# design.net
KiCad netlist of a schematic drawn in Altium Designer
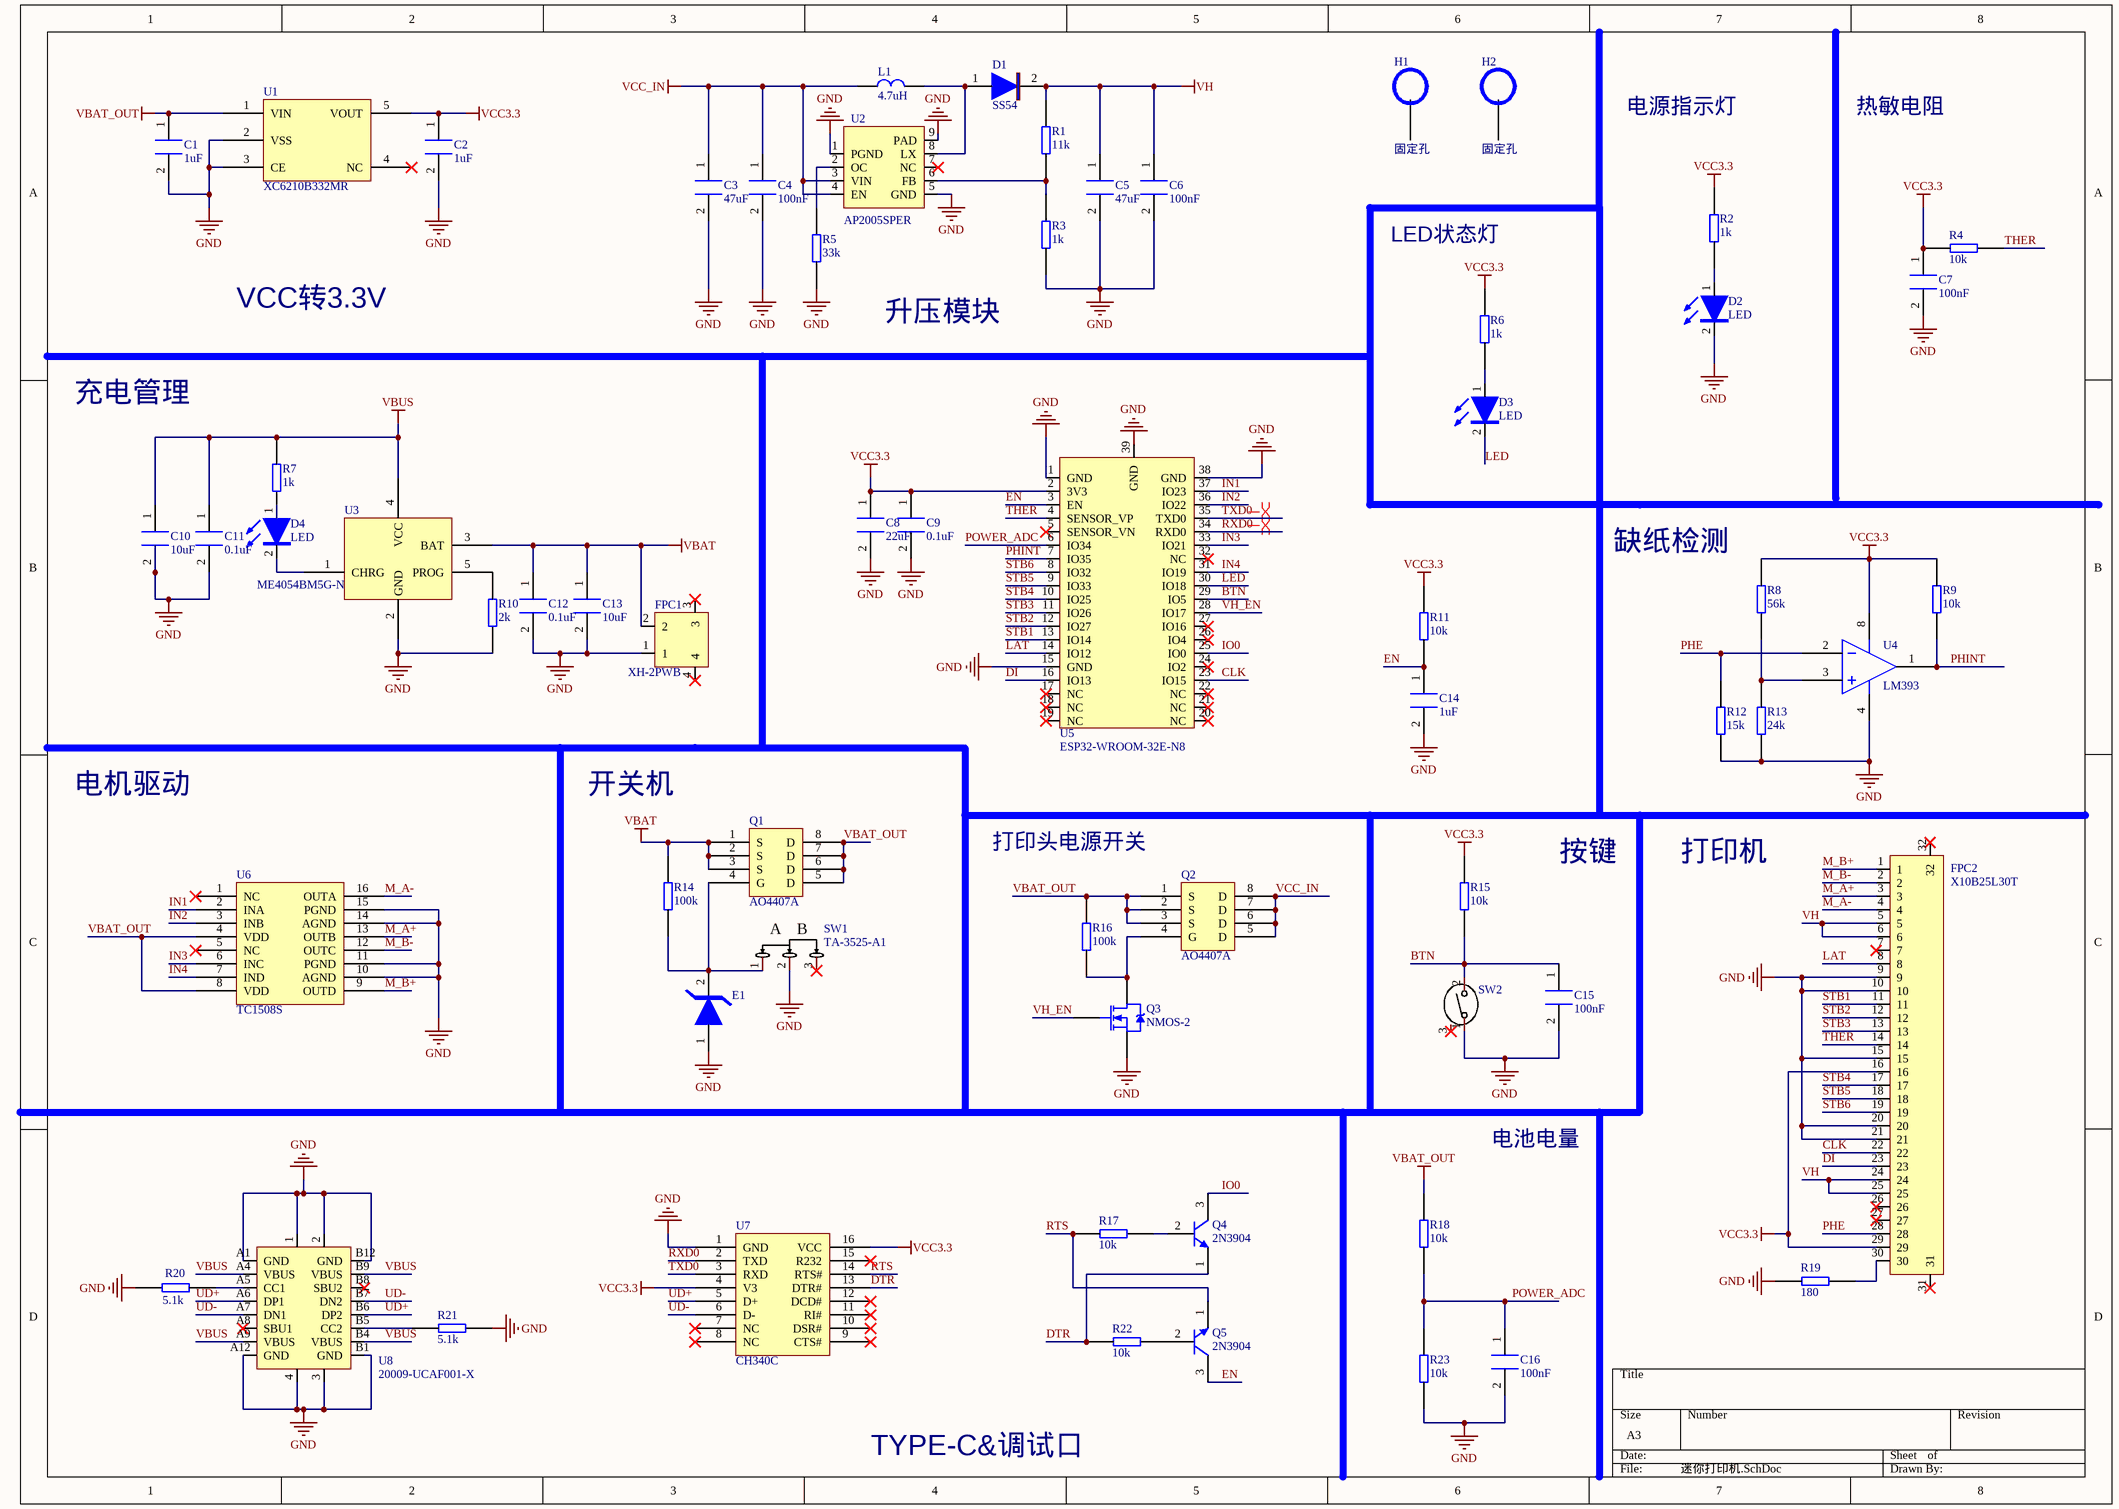
[diagram p0: 迷你打印机.SchDoc]

(export (version "E")
  (design (tool "Eeschema 10.0.6"))
  (components
    (comp (ref "C1")
      (value "1uF")
      (footprint "0603C")
      (description "电容")
      (libsource (lib "迷你打印机") (part "CAP"))
    )
    (comp (ref "C2")
      (value "1uF")
      (footprint "0603C")
      (description "电容")
      (libsource (lib "迷你打印机") (part "CAP"))
    )
    (comp (ref "C3")
      (value "47uF")
      (footprint "0603C")
      (description "电容")
      (libsource (lib "迷你打印机") (part "CAP"))
    )
    (comp (ref "C4")
      (value "100nF")
      (footprint "0603C")
      (description "电容")
      (libsource (lib "迷你打印机") (part "CAP"))
    )
    (comp (ref "C5")
      (value "47uF")
      (footprint "0603C")
      (description "电容")
      (libsource (lib "迷你打印机") (part "CAP"))
    )
    (comp (ref "C6")
      (value "100nF")
      (footprint "0603C")
      (description "电容")
      (libsource (lib "迷你打印机") (part "CAP"))
    )
    (comp (ref "C7")
      (value "100nF")
      (footprint "0603C")
      (description "电容")
      (libsource (lib "迷你打印机") (part "CAP"))
    )
    (comp (ref "C8")
      (value "22uF")
      (footprint "0603C")
      (description "电容")
      (libsource (lib "迷你打印机") (part "CAP"))
    )
    (comp (ref "C9")
      (value "0.1uF")
      (footprint "0603C")
      (description "电容")
      (libsource (lib "迷你打印机") (part "CAP"))
    )
    (comp (ref "C10")
      (value "10uF")
      (footprint "0603C")
      (description "电容")
      (libsource (lib "迷你打印机") (part "CAP"))
    )
    (comp (ref "C11")
      (value "0.1uF")
      (footprint "0603C")
      (description "电容")
      (libsource (lib "迷你打印机") (part "CAP"))
    )
    (comp (ref "C12")
      (value "0.1uF")
      (footprint "0603C")
      (description "电容")
      (libsource (lib "迷你打印机") (part "CAP"))
    )
    (comp (ref "C13")
      (value "10uF")
      (footprint "0603C")
      (description "电容")
      (libsource (lib "迷你打印机") (part "CAP"))
    )
    (comp (ref "C14")
      (value "1uF")
      (footprint "0603C")
      (description "电容")
      (libsource (lib "迷你打印机") (part "CAP"))
    )
    (comp (ref "C15")
      (value "100nF")
      (footprint "0603C")
      (description "电容")
      (libsource (lib "迷你打印机") (part "CAP"))
    )
    (comp (ref "C16")
      (value "100nF")
      (footprint "0603C")
      (description "电容")
      (libsource (lib "迷你打印机") (part "CAP"))
    )
    (comp (ref "D1")
      (value "SS54")
      (footprint "SMA")
      (description "二极管")
      (libsource (lib "迷你打印机") (part "SS54"))
    )
    (comp (ref "D2") (value "LED") (footprint "0805D") (libsource (lib "迷你打印机") (part "LED")))
    (comp (ref "D3") (value "LED") (footprint "0805D") (libsource (lib "迷你打印机") (part "LED")))
    (comp (ref "D4") (value "LED") (footprint "0805D") (libsource (lib "迷你打印机") (part "LED")))
    (comp (ref "E1") (value "单向ESD") (footprint "SOD323") (libsource (lib "迷你打印机") (part "单向ESD")))
    (comp (ref "FPC1")
      (value "XH-2PWB")
      (footprint "CONN-SMD_2P-P2.50_XH-2PWB")
      (libsource (lib "迷你打印机") (part "XH-2PWB"))
    )
    (comp (ref "FPC2")
      (value "X10B25L30T")
      (footprint "FPC-SMD_X10B25U30T")
      (fields (field (name "MANUFACTURER") "XKB Connectivity(中国星坤)"))
      (libsource (lib "迷你打印机") (part "X10B25L30T"))
    )
    (comp (ref "H1") (value "固定孔") (footprint "铜柱孔3") (libsource (lib "智能车主板") (part "固定孔")))
    (comp (ref "H2") (value "固定孔") (footprint "铜柱孔3") (libsource (lib "智能车主板") (part "固定孔")))
    (comp (ref "L1")
      (value "4.7uH")
      (footprint "IND-SMD_L5.4-W5.2_FXL0530")
      (description "电感")
      (libsource (lib "迷你打印机") (part "INDUCTOR2"))
    )
    (comp (ref "Q1")
      (value "AO4407A")
      (footprint "SOP8")
      (description "二极管")
      (libsource (lib "迷你打印机") (part "AO4407A"))
    )
    (comp (ref "Q2")
      (value "AO4407A")
      (footprint "SOP8")
      (description "二极管")
      (libsource (lib "迷你打印机") (part "AO4407A"))
    )
    (comp (ref "Q3")
      (value "NMOS-2")
      (footprint "SOT23-3")
      (description "N-Channel Power MOSFET")
      (fields (field (name "PUBLISHER") "Altium Limited"))
      (libsource (lib "Miscellaneous Devices") (part "NMOS-2"))
    )
    (comp (ref "Q4")
      (value "2N3904")
      (footprint "SOT23-3")
      (description "NPN General Purpose Amplifier")
      (fields (field (name "PUBLISHER") "Altium Limited"))
      (libsource (lib "迷你打印机") (part "2N3904"))
    )
    (comp (ref "Q5")
      (value "2N3904")
      (footprint "SOT23-3")
      (description "NPN General Purpose Amplifier")
      (fields (field (name "PUBLISHER") "Altium Limited"))
      (libsource (lib "迷你打印机") (part "2N3904"))
    )
    (comp (ref "R1")
      (value "11k")
      (footprint "0603R")
      (description "电阻")
      (libsource (lib "迷你打印机") (part "RES"))
    )
    (comp (ref "R2")
      (value "1k")
      (footprint "0603R")
      (description "电阻")
      (libsource (lib "迷你打印机") (part "RES"))
    )
    (comp (ref "R3")
      (value "1k")
      (footprint "0603R")
      (description "电阻")
      (libsource (lib "迷你打印机") (part "RES"))
    )
    (comp (ref "R4")
      (value "10k")
      (footprint "0603R")
      (description "电阻")
      (libsource (lib "迷你打印机") (part "RES"))
    )
    (comp (ref "R5")
      (value "33k")
      (footprint "0603R")
      (description "电阻")
      (libsource (lib "迷你打印机") (part "RES"))
    )
    (comp (ref "R6")
      (value "1k")
      (footprint "0603R")
      (description "电阻")
      (libsource (lib "迷你打印机") (part "RES"))
    )
    (comp (ref "R7")
      (value "1k")
      (footprint "0603R")
      (description "电阻")
      (libsource (lib "迷你打印机") (part "RES"))
    )
    (comp (ref "R8")
      (value "56k")
      (footprint "0603R")
      (description "电阻")
      (libsource (lib "迷你打印机") (part "RES"))
    )
    (comp (ref "R9")
      (value "10k")
      (footprint "0603R")
      (description "电阻")
      (libsource (lib "迷你打印机") (part "RES"))
    )
    (comp (ref "R10")
      (value "2k")
      (footprint "0603R")
      (description "电阻")
      (libsource (lib "迷你打印机") (part "RES"))
    )
    (comp (ref "R11")
      (value "10k")
      (footprint "0603R")
      (description "电阻")
      (libsource (lib "迷你打印机") (part "RES"))
    )
    (comp (ref "R12")
      (value "15k")
      (footprint "0603R")
      (description "电阻")
      (libsource (lib "迷你打印机") (part "RES"))
    )
    (comp (ref "R13")
      (value "24k")
      (footprint "0603R")
      (description "电阻")
      (libsource (lib "迷你打印机") (part "RES"))
    )
    (comp (ref "R14")
      (value "100k")
      (footprint "0603R")
      (description "电阻")
      (libsource (lib "迷你打印机") (part "RES"))
    )
    (comp (ref "R15")
      (value "10k")
      (footprint "0603R")
      (description "电阻")
      (libsource (lib "迷你打印机") (part "RES"))
    )
    (comp (ref "R16")
      (value "100k")
      (footprint "0603R")
      (description "电阻")
      (libsource (lib "迷你打印机") (part "RES"))
    )
    (comp (ref "R17")
      (value "10k")
      (footprint "0603R")
      (description "电阻")
      (libsource (lib "迷你打印机") (part "RES"))
    )
    (comp (ref "R18")
      (value "10k")
      (footprint "0603R")
      (description "电阻")
      (libsource (lib "迷你打印机") (part "RES"))
    )
    (comp (ref "R19")
      (value "180")
      (footprint "0603R")
      (description "电阻")
      (libsource (lib "迷你打印机") (part "RES"))
    )
    (comp (ref "R20")
      (value "5.1k")
      (footprint "0603R")
      (description "电阻")
      (libsource (lib "迷你打印机") (part "RES"))
    )
    (comp (ref "R21")
      (value "5.1k")
      (footprint "0603R")
      (description "电阻")
      (libsource (lib "迷你打印机") (part "RES"))
    )
    (comp (ref "R22")
      (value "10k")
      (footprint "0603R")
      (description "电阻")
      (libsource (lib "迷你打印机") (part "RES"))
    )
    (comp (ref "R23")
      (value "10k")
      (footprint "0603R")
      (description "电阻")
      (libsource (lib "迷你打印机") (part "RES"))
    )
    (comp (ref "SW1")
      (value "TA-3525-A1")
      (footprint "SW-SMD_3P-L9.1-W3.5-P2.50-EH6.8")
      (fields (field (name "MANUFACTURER") "Yuandi(元迪)") (field (name "NAME") "TA-3525-A1"))
      (libsource (lib "迷你打印机") (part "TA-3525-A1"))
    )
    (comp (ref "SW2")
      (value "TS4538B3JTP 250gf 121")
      (footprint "KEY-SMD_3P-L4.5-W3.8-P3.00-LS4.5-BL")
      (description "按键")
      (fields (field (name "MANUFACTURER") "SHOU HAN(首韩)"))
      (libsource (lib "迷你打印机") (part "TS4538B3JTP 250gf 121"))
    )
    (comp (ref "U1")
      (value "XC6210B332MR")
      (footprint "SOT23-5")
      (description "IC")
      (libsource (lib "迷你打印机") (part "XC6210B332MR"))
    )
    (comp (ref "U2")
      (value "AP2005SPER")
      (footprint "ESOP-8_L4.9-W3.9-P1.27-LS6.0-BL-EP")
      (description "IC")
      (fields (field (name "MANUFACTURER") "chipown(芯朋微电子)"))
      (libsource (lib "迷你打印机") (part "AP2005SPER"))
    )
    (comp (ref "U3")
      (value "ME4054BM5G-N")
      (footprint "SOT23-5")
      (description "IC")
      (libsource (lib "迷你打印机") (part "ME4054BM5G-N"))
    )
    (comp (ref "U4")
      (value "LM393")
      (footprint "SOP8")
      (description "放大器")
      (fields (field (name "PUBLISHER") "Altium Limited"))
      (libsource (lib "迷你打印机") (part "LM393"))
    )
    (comp (ref "U5")
      (value "ESP32-WROOM-32E-N8")
      (footprint "WIFI-SMD_ESP32-WROOM-32E")
      (description "IC")
      (fields (field (name "MANUFACTURER") "ESPRESSIF(乐鑫)"))
      (libsource (lib "迷你打印机") (part "ESP32-WROOM-32E-N8"))
    )
    (comp (ref "U6")
      (value "TC1508S")
      (footprint "SOP16")
      (description "IC")
      (libsource (lib "迷你打印机") (part "TC1508S"))
    )
    (comp (ref "U7")
      (value "CH340C")
      (footprint "SOP16")
      (description "IC")
      (libsource (lib "迷你打印机") (part "CH340C"))
    )
    (comp (ref "U8")
      (value "20009-UCAF001-X")
      (footprint "TYPE-C-SMD_20009-UCAF001-X")
      (description "IC")
      (fields (field (name "MANUFACTURER") "MINTRON(明硕)"))
      (libsource (lib "迷你打印机") (part "20009-UCAF001-X"))
    )
  )
  (nets
    (net (code "1") (name "/BTN") (class "Default")
      (node (ref "C15") (pin "1") (pinfunction "1_1") (pintype "passive"))
      (node (ref "R15") (pin "1") (pinfunction "1_1") (pintype "passive"))
      (node (ref "SW2") (pin "2") (pinfunction "2_2") (pintype "passive"))
      (node (ref "U5") (pin "29") (pinfunction "IO5_29") (pintype "passive"))
    )
    (net (code "2") (name "/CLK") (class "Default")
      (node (ref "FPC2") (pin "22") (pinfunction "22_22") (pintype "passive"))
      (node (ref "U5") (pin "23") (pinfunction "IO15_23") (pintype "passive"))
    )
    (net (code "3") (name "/DI") (class "Default")
      (node (ref "FPC2") (pin "23") (pinfunction "23_23") (pintype "passive"))
      (node (ref "U5") (pin "16") (pinfunction "IO13_16") (pintype "passive"))
    )
    (net (code "4") (name "/DTR") (class "Default")
      (node (ref "Q4") (pin "1") (pinfunction "1_1") (pintype "passive"))
      (node (ref "R22") (pin "2") (pinfunction "2_2") (pintype "passive"))
      (node (ref "U7") (pin "13") (pinfunction "DTR#_13") (pintype "passive"))
    )
    (net (code "5") (name "/EN") (class "Default")
      (node (ref "C14") (pin "1") (pinfunction "1_1") (pintype "passive"))
      (node (ref "Q5") (pin "3") (pinfunction "3_3") (pintype "passive"))
      (node (ref "R11") (pin "2") (pinfunction "2_2") (pintype "passive"))
      (node (ref "U5") (pin "3") (pinfunction "EN_3") (pintype "passive"))
    )
    (net (code "6") (name "/IN1") (class "Default")
      (node (ref "U5") (pin "37") (pinfunction "IO23_37") (pintype "passive"))
      (node (ref "U6") (pin "2") (pinfunction "INA_2") (pintype "passive"))
    )
    (net (code "7") (name "/IN2") (class "Default")
      (node (ref "U5") (pin "36") (pinfunction "IO22_36") (pintype "passive"))
      (node (ref "U6") (pin "3") (pinfunction "INB_3") (pintype "passive"))
    )
    (net (code "8") (name "/IN3") (class "Default")
      (node (ref "U5") (pin "33") (pinfunction "IO21_33") (pintype "passive"))
      (node (ref "U6") (pin "6") (pinfunction "INC_6") (pintype "passive"))
    )
    (net (code "9") (name "/IN4") (class "Default")
      (node (ref "U5") (pin "31") (pinfunction "IO19_31") (pintype "passive"))
      (node (ref "U6") (pin "7") (pinfunction "IND_7") (pintype "passive"))
    )
    (net (code "10") (name "/IO0") (class "Default")
      (node (ref "Q4") (pin "3") (pinfunction "3_3") (pintype "passive"))
      (node (ref "U5") (pin "25") (pinfunction "IO0_25") (pintype "passive"))
    )
    (net (code "11") (name "/LAT") (class "Default")
      (node (ref "FPC2") (pin "8") (pinfunction "8_8") (pintype "passive"))
      (node (ref "U5") (pin "14") (pinfunction "IO12_14") (pintype "passive"))
    )
    (net (code "12") (name "/LED") (class "Default")
      (node (ref "D3") (pin "2") (pinfunction "2_2") (pintype "passive"))
      (node (ref "U5") (pin "30") (pinfunction "IO18_30") (pintype "passive"))
    )
    (net (code "13") (name "/M_A+") (class "Default")
      (node (ref "FPC2") (pin "3") (pinfunction "3_3") (pintype "passive"))
      (node (ref "U6") (pin "13") (pinfunction "OUTB_13") (pintype "passive"))
    )
    (net (code "14") (name "/M_A-") (class "Default")
      (node (ref "FPC2") (pin "4") (pinfunction "4_4") (pintype "passive"))
      (node (ref "U6") (pin "16") (pinfunction "OUTA_16") (pintype "passive"))
    )
    (net (code "15") (name "/M_B+") (class "Default")
      (node (ref "FPC2") (pin "1") (pinfunction "1_1") (pintype "passive"))
      (node (ref "U6") (pin "9") (pinfunction "OUTD_9") (pintype "passive"))
    )
    (net (code "16") (name "/M_B-") (class "Default")
      (node (ref "FPC2") (pin "2") (pinfunction "2_2") (pintype "passive"))
      (node (ref "U6") (pin "12") (pinfunction "OUTC_12") (pintype "passive"))
    )
    (net (code "17") (name "/PHE") (class "Default")
      (node (ref "FPC2") (pin "28") (pinfunction "28_28") (pintype "passive"))
      (node (ref "R12") (pin "2") (pinfunction "2_2") (pintype "passive"))
      (node (ref "U4") (pin "2") (pinfunction "IN-_2") (pintype "passive"))
    )
    (net (code "18") (name "/PHINT") (class "Default")
      (node (ref "R9") (pin "1") (pinfunction "1_1") (pintype "passive"))
      (node (ref "U4") (pin "1") (pinfunction "OUT_1") (pintype "passive"))
      (node (ref "U5") (pin "7") (pinfunction "IO35_7") (pintype "passive"))
    )
    (net (code "19") (name "/POWER_ADC") (class "Default")
      (node (ref "C16") (pin "1") (pinfunction "1_1") (pintype "passive"))
      (node (ref "R18") (pin "2") (pinfunction "2_2") (pintype "passive"))
      (node (ref "R23") (pin "1") (pinfunction "1_1") (pintype "passive"))
      (node (ref "U5") (pin "6") (pinfunction "IO34_6") (pintype "passive"))
    )
    (net (code "20") (name "/RTS") (class "Default")
      (node (ref "Q5") (pin "1") (pinfunction "1_1") (pintype "passive"))
      (node (ref "R17") (pin "2") (pinfunction "2_2") (pintype "passive"))
      (node (ref "U7") (pin "14") (pinfunction "RTS#_14") (pintype "passive"))
    )
    (net (code "21") (name "/RXD0") (class "Default")
      (node (ref "U5") (pin "34") (pinfunction "RXD0_34") (pintype "passive"))
      (node (ref "U7") (pin "2") (pinfunction "TXD_2") (pintype "passive"))
    )
    (net (code "22") (name "/STB1") (class "Default")
      (node (ref "FPC2") (pin "11") (pinfunction "11_11") (pintype "passive"))
      (node (ref "U5") (pin "13") (pinfunction "IO14_13") (pintype "passive"))
    )
    (net (code "23") (name "/STB2") (class "Default")
      (node (ref "FPC2") (pin "12") (pinfunction "12_12") (pintype "passive"))
      (node (ref "U5") (pin "12") (pinfunction "IO27_12") (pintype "passive"))
    )
    (net (code "24") (name "/STB3") (class "Default")
      (node (ref "FPC2") (pin "13") (pinfunction "13_13") (pintype "passive"))
      (node (ref "U5") (pin "11") (pinfunction "IO26_11") (pintype "passive"))
    )
    (net (code "25") (name "/STB4") (class "Default")
      (node (ref "FPC2") (pin "17") (pinfunction "17_17") (pintype "passive"))
      (node (ref "U5") (pin "10") (pinfunction "IO25_10") (pintype "passive"))
    )
    (net (code "26") (name "/STB5") (class "Default")
      (node (ref "FPC2") (pin "18") (pinfunction "18_18") (pintype "passive"))
      (node (ref "U5") (pin "9") (pinfunction "IO33_9") (pintype "passive"))
    )
    (net (code "27") (name "/STB6") (class "Default")
      (node (ref "FPC2") (pin "19") (pinfunction "19_19") (pintype "passive"))
      (node (ref "U5") (pin "8") (pinfunction "IO32_8") (pintype "passive"))
    )
    (net (code "28") (name "/THER") (class "Default")
      (node (ref "FPC2") (pin "14") (pinfunction "14_14") (pintype "passive"))
      (node (ref "R4") (pin "1") (pinfunction "1_1") (pintype "passive"))
      (node (ref "U5") (pin "4") (pinfunction "SENSOR_VP_4") (pintype "passive"))
    )
    (net (code "29") (name "/TXD0") (class "Default")
      (node (ref "U5") (pin "35") (pinfunction "TXD0_35") (pintype "passive"))
      (node (ref "U7") (pin "3") (pinfunction "RXD_3") (pintype "passive"))
    )
    (net (code "30") (name "/UD+") (class "Default")
      (node (ref "U7") (pin "5") (pinfunction "D+_5") (pintype "passive"))
      (node (ref "U8") (pin "A6") (pinfunction "DP1_A6") (pintype "passive"))
      (node (ref "U8") (pin "B6") (pinfunction "DP2_B6") (pintype "passive"))
    )
    (net (code "31") (name "/UD-") (class "Default")
      (node (ref "U7") (pin "6") (pinfunction "D-_6") (pintype "passive"))
      (node (ref "U8") (pin "A7") (pinfunction "DN1_A7") (pintype "passive"))
      (node (ref "U8") (pin "B7") (pinfunction "DN2_B7") (pintype "passive"))
    )
    (net (code "32") (name "/VH_EN") (class "Default")
      (node (ref "Q3") (pin "1") (pinfunction "G_1") (pintype "passive"))
      (node (ref "U5") (pin "28") (pinfunction "IO17_28") (pintype "passive"))
    )
    (net (code "33") (name "GND") (class "Default")
      (node (ref "C1") (pin "2") (pinfunction "2_2") (pintype "passive"))
      (node (ref "C10") (pin "2") (pinfunction "2_2") (pintype "passive"))
      (node (ref "C11") (pin "2") (pinfunction "2_2") (pintype "passive"))
      (node (ref "C12") (pin "2") (pinfunction "2_2") (pintype "passive"))
      (node (ref "C13") (pin "2") (pinfunction "2_2") (pintype "passive"))
      (node (ref "C14") (pin "2") (pinfunction "2_2") (pintype "passive"))
      (node (ref "C15") (pin "2") (pinfunction "2_2") (pintype "passive"))
      (node (ref "C16") (pin "2") (pinfunction "2_2") (pintype "passive"))
      (node (ref "C2") (pin "2") (pinfunction "2_2") (pintype "passive"))
      (node (ref "C3") (pin "2") (pinfunction "2_2") (pintype "passive"))
      (node (ref "C4") (pin "2") (pinfunction "2_2") (pintype "passive"))
      (node (ref "C5") (pin "2") (pinfunction "2_2") (pintype "passive"))
      (node (ref "C6") (pin "2") (pinfunction "2_2") (pintype "passive"))
      (node (ref "C7") (pin "2") (pinfunction "2_2") (pintype "passive"))
      (node (ref "C8") (pin "2") (pinfunction "2_2") (pintype "passive"))
      (node (ref "C9") (pin "2") (pinfunction "2_2") (pintype "passive"))
      (node (ref "D2") (pin "2") (pinfunction "2_2") (pintype "passive"))
      (node (ref "E1") (pin "1") (pinfunction "1_1") (pintype "passive"))
      (node (ref "FPC1") (pin "1") (pinfunction "1_1") (pintype "passive"))
      (node (ref "FPC2") (pin "10") (pinfunction "10_10") (pintype "passive"))
      (node (ref "FPC2") (pin "15") (pinfunction "15_15") (pintype "passive"))
      (node (ref "FPC2") (pin "20") (pinfunction "20_20") (pintype "passive"))
      (node (ref "FPC2") (pin "21") (pinfunction "21_21") (pintype "passive"))
      (node (ref "FPC2") (pin "9") (pinfunction "9_9") (pintype "passive"))
      (node (ref "Q3") (pin "3") (pinfunction "S_3") (pintype "passive"))
      (node (ref "R10") (pin "1") (pinfunction "1_1") (pintype "passive"))
      (node (ref "R12") (pin "1") (pinfunction "1_1") (pintype "passive"))
      (node (ref "R13") (pin "1") (pinfunction "1_1") (pintype "passive"))
      (node (ref "R19") (pin "2") (pinfunction "2_2") (pintype "passive"))
      (node (ref "R20") (pin "1") (pinfunction "1_1") (pintype "passive"))
      (node (ref "R21") (pin "1") (pinfunction "1_1") (pintype "passive"))
      (node (ref "R23") (pin "2") (pinfunction "2_2") (pintype "passive"))
      (node (ref "R3") (pin "2") (pinfunction "2_2") (pintype "passive"))
      (node (ref "R5") (pin "2") (pinfunction "2_2") (pintype "passive"))
      (node (ref "SW1") (pin "2") (pinfunction "2_2") (pintype "passive"))
      (node (ref "SW2") (pin "1") (pinfunction "1_1") (pintype "passive"))
      (node (ref "U1") (pin "2") (pinfunction "VSS_2") (pintype "passive"))
      (node (ref "U1") (pin "3") (pinfunction "CE_3") (pintype "passive"))
      (node (ref "U2") (pin "1") (pinfunction "PGND_1") (pintype "passive"))
      (node (ref "U2") (pin "5") (pinfunction "GND_5") (pintype "passive"))
      (node (ref "U2") (pin "9") (pinfunction "PAD_9") (pintype "passive"))
      (node (ref "U3") (pin "2") (pinfunction "GND_2") (pintype "passive"))
      (node (ref "U4") (pin "4") (pinfunction "V-_4") (pintype "power_in"))
      (node (ref "U5") (pin "1") (pinfunction "GND_1") (pintype "passive"))
      (node (ref "U5") (pin "15") (pinfunction "GND_15") (pintype "passive"))
      (node (ref "U5") (pin "38") (pinfunction "GND_38") (pintype "passive"))
      (node (ref "U5") (pin "39") (pinfunction "GND_39") (pintype "passive"))
      (node (ref "U6") (pin "10") (pinfunction "AGND_10") (pintype "passive"))
      (node (ref "U6") (pin "11") (pinfunction "PGND_11") (pintype "passive"))
      (node (ref "U6") (pin "14") (pinfunction "AGND_14") (pintype "passive"))
      (node (ref "U6") (pin "15") (pinfunction "PGND_15") (pintype "passive"))
      (node (ref "U7") (pin "1") (pinfunction "GND_1") (pintype "passive"))
      (node (ref "U8") (pin "1") (pintype "passive"))
      (node (ref "U8") (pin "2") (pintype "passive"))
      (node (ref "U8") (pin "3") (pintype "passive"))
      (node (ref "U8") (pin "4") (pintype "passive"))
      (node (ref "U8") (pin "A1") (pinfunction "GND_A1") (pintype "passive"))
      (node (ref "U8") (pin "A12") (pinfunction "GND_A12") (pintype "passive"))
      (node (ref "U8") (pin "B1") (pinfunction "GND_B1") (pintype "passive"))
      (node (ref "U8") (pin "B12") (pinfunction "GND_B12") (pintype "passive"))
    )
    (net (code "34") (name "Net-(D2-Pad1)") (class "Default")
      (node (ref "D2") (pin "1") (pinfunction "1_1") (pintype "passive"))
      (node (ref "R2") (pin "2") (pinfunction "2_2") (pintype "passive"))
    )
    (net (code "35") (name "Net-(D3-Pad1)") (class "Default")
      (node (ref "D3") (pin "1") (pinfunction "1_1") (pintype "passive"))
      (node (ref "R6") (pin "2") (pinfunction "2_2") (pintype "passive"))
    )
    (net (code "36") (name "Net-(D4-Pad1)") (class "Default")
      (node (ref "D4") (pin "1") (pinfunction "1_1") (pintype "passive"))
      (node (ref "R7") (pin "1") (pinfunction "1_1") (pintype "passive"))
    )
    (net (code "37") (name "Net-(FPC2-Pad30)") (class "Default")
      (node (ref "FPC2") (pin "30") (pinfunction "30_30") (pintype "passive"))
      (node (ref "R19") (pin "1") (pinfunction "1_1") (pintype "passive"))
    )
    (net (code "38") (name "Net-(Q1-G)") (class "Default")
      (node (ref "E1") (pin "2") (pinfunction "2_2") (pintype "passive"))
      (node (ref "Q1") (pin "4") (pinfunction "G_4") (pintype "passive"))
      (node (ref "R14") (pin "2") (pinfunction "2_2") (pintype "passive"))
      (node (ref "SW1") (pin "1") (pinfunction "1_1") (pintype "passive"))
    )
    (net (code "39") (name "Net-(Q2-G)") (class "Default")
      (node (ref "Q2") (pin "4") (pinfunction "G_4") (pintype "passive"))
      (node (ref "Q3") (pin "2") (pinfunction "D_2") (pintype "passive"))
      (node (ref "R16") (pin "2") (pinfunction "2_2") (pintype "passive"))
    )
    (net (code "40") (name "Net-(Q4-Pad2)") (class "Default")
      (node (ref "Q4") (pin "2") (pinfunction "2_2") (pintype "passive"))
      (node (ref "R17") (pin "1") (pinfunction "1_1") (pintype "passive"))
    )
    (net (code "41") (name "Net-(Q5-Pad2)") (class "Default")
      (node (ref "Q5") (pin "2") (pinfunction "2_2") (pintype "passive"))
      (node (ref "R22") (pin "1") (pinfunction "1_1") (pintype "passive"))
    )
    (net (code "42") (name "Net-(U2-FB)") (class "Default")
      (node (ref "R1") (pin "2") (pinfunction "2_2") (pintype "passive"))
      (node (ref "R3") (pin "1") (pinfunction "1_1") (pintype "passive"))
      (node (ref "U2") (pin "6") (pinfunction "FB_6") (pintype "passive"))
    )
    (net (code "43") (name "Net-(U2-LX)") (class "Default")
      (node (ref "D1") (pin "1") (pinfunction "1_1") (pintype "passive"))
      (node (ref "L1") (pin "2") (pinfunction "2_2") (pintype "passive"))
      (node (ref "U2") (pin "8") (pinfunction "LX_8") (pintype "passive"))
    )
    (net (code "44") (name "Net-(U2-OC)") (class "Default")
      (node (ref "R5") (pin "1") (pinfunction "1_1") (pintype "passive"))
      (node (ref "U2") (pin "2") (pinfunction "OC_2") (pintype "passive"))
    )
    (net (code "45") (name "Net-(U3-CHRG)") (class "Default")
      (node (ref "D4") (pin "2") (pinfunction "2_2") (pintype "passive"))
      (node (ref "U3") (pin "1") (pinfunction "CHRG_1") (pintype "passive"))
    )
    (net (code "46") (name "Net-(U3-PROG)") (class "Default")
      (node (ref "R10") (pin "2") (pinfunction "2_2") (pintype "passive"))
      (node (ref "U3") (pin "5") (pinfunction "PROG_5") (pintype "passive"))
    )
    (net (code "47") (name "Net-(U4-IN+)") (class "Default")
      (node (ref "R13") (pin "2") (pinfunction "2_2") (pintype "passive"))
      (node (ref "R8") (pin "1") (pinfunction "1_1") (pintype "passive"))
      (node (ref "U4") (pin "3") (pinfunction "IN+_3") (pintype "passive"))
    )
    (net (code "48") (name "Net-(U8-CC1)") (class "Default")
      (node (ref "R20") (pin "2") (pinfunction "2_2") (pintype "passive"))
      (node (ref "U8") (pin "A5") (pinfunction "CC1_A5") (pintype "passive"))
    )
    (net (code "49") (name "Net-(U8-CC2)") (class "Default")
      (node (ref "R21") (pin "2") (pinfunction "2_2") (pintype "passive"))
      (node (ref "U8") (pin "B5") (pinfunction "CC2_B5") (pintype "passive"))
    )
    (net (code "50") (name "VBAT") (class "Default")
      (node (ref "C12") (pin "1") (pinfunction "1_1") (pintype "passive"))
      (node (ref "C13") (pin "1") (pinfunction "1_1") (pintype "passive"))
      (node (ref "FPC1") (pin "2") (pinfunction "2_2") (pintype "passive"))
      (node (ref "Q1") (pin "1") (pinfunction "S_1") (pintype "passive"))
      (node (ref "Q1") (pin "2") (pinfunction "S_2") (pintype "passive"))
      (node (ref "Q1") (pin "3") (pinfunction "S_3") (pintype "passive"))
      (node (ref "R14") (pin "1") (pinfunction "1_1") (pintype "passive"))
      (node (ref "U3") (pin "3") (pinfunction "BAT_3") (pintype "passive"))
    )
    (net (code "51") (name "VBAT_OUT") (class "Default")
      (node (ref "C1") (pin "1") (pinfunction "1_1") (pintype "passive"))
      (node (ref "Q1") (pin "5") (pinfunction "D_5") (pintype "passive"))
      (node (ref "Q1") (pin "6") (pinfunction "D_6") (pintype "passive"))
      (node (ref "Q1") (pin "7") (pinfunction "D_7") (pintype "passive"))
      (node (ref "Q1") (pin "8") (pinfunction "D_8") (pintype "passive"))
      (node (ref "Q2") (pin "1") (pinfunction "S_1") (pintype "passive"))
      (node (ref "Q2") (pin "2") (pinfunction "S_2") (pintype "passive"))
      (node (ref "Q2") (pin "3") (pinfunction "S_3") (pintype "passive"))
      (node (ref "R16") (pin "1") (pinfunction "1_1") (pintype "passive"))
      (node (ref "R18") (pin "1") (pinfunction "1_1") (pintype "passive"))
      (node (ref "U1") (pin "1") (pinfunction "VIN_1") (pintype "passive"))
      (node (ref "U6") (pin "4") (pinfunction "VDD_4") (pintype "passive"))
      (node (ref "U6") (pin "8") (pinfunction "VDD_8") (pintype "passive"))
    )
    (net (code "52") (name "VBUS") (class "Default")
      (node (ref "C10") (pin "1") (pinfunction "1_1") (pintype "passive"))
      (node (ref "C11") (pin "1") (pinfunction "1_1") (pintype "passive"))
      (node (ref "R7") (pin "2") (pinfunction "2_2") (pintype "passive"))
      (node (ref "U3") (pin "4") (pinfunction "VCC_4") (pintype "passive"))
      (node (ref "U8") (pin "A4") (pinfunction "VBUS_A4") (pintype "passive"))
      (node (ref "U8") (pin "A9") (pinfunction "VBUS_A9") (pintype "passive"))
      (node (ref "U8") (pin "B4") (pinfunction "VBUS_B4") (pintype "passive"))
      (node (ref "U8") (pin "B9") (pinfunction "VBUS_B9") (pintype "passive"))
    )
    (net (code "53") (name "VCC3.3") (class "Default")
      (node (ref "C2") (pin "1") (pinfunction "1_1") (pintype "passive"))
      (node (ref "C7") (pin "1") (pinfunction "1_1") (pintype "passive"))
      (node (ref "C8") (pin "1") (pinfunction "1_1") (pintype "passive"))
      (node (ref "C9") (pin "1") (pinfunction "1_1") (pintype "passive"))
      (node (ref "FPC2") (pin "16") (pinfunction "16_16") (pintype "passive"))
      (node (ref "FPC2") (pin "29") (pinfunction "29_29") (pintype "passive"))
      (node (ref "R11") (pin "1") (pinfunction "1_1") (pintype "passive"))
      (node (ref "R15") (pin "2") (pinfunction "2_2") (pintype "passive"))
      (node (ref "R2") (pin "1") (pinfunction "1_1") (pintype "passive"))
      (node (ref "R4") (pin "2") (pinfunction "2_2") (pintype "passive"))
      (node (ref "R6") (pin "1") (pinfunction "1_1") (pintype "passive"))
      (node (ref "R8") (pin "2") (pinfunction "2_2") (pintype "passive"))
      (node (ref "R9") (pin "2") (pinfunction "2_2") (pintype "passive"))
      (node (ref "U1") (pin "5") (pinfunction "VOUT_5") (pintype "passive"))
      (node (ref "U4") (pin "8") (pinfunction "V+_8") (pintype "power_in"))
      (node (ref "U5") (pin "2") (pinfunction "3V3_2") (pintype "passive"))
      (node (ref "U7") (pin "16") (pinfunction "VCC_16") (pintype "passive"))
      (node (ref "U7") (pin "4") (pinfunction "V3_4") (pintype "passive"))
    )
    (net (code "54") (name "VCC_IN") (class "Default")
      (node (ref "C3") (pin "1") (pinfunction "1_1") (pintype "passive"))
      (node (ref "C4") (pin "1") (pinfunction "1_1") (pintype "passive"))
      (node (ref "L1") (pin "1") (pinfunction "1_1") (pintype "passive"))
      (node (ref "Q2") (pin "5") (pinfunction "D_5") (pintype "passive"))
      (node (ref "Q2") (pin "6") (pinfunction "D_6") (pintype "passive"))
      (node (ref "Q2") (pin "7") (pinfunction "D_7") (pintype "passive"))
      (node (ref "Q2") (pin "8") (pinfunction "D_8") (pintype "passive"))
      (node (ref "U2") (pin "3") (pinfunction "VIN_3") (pintype "passive"))
      (node (ref "U2") (pin "4") (pinfunction "EN_4") (pintype "passive"))
    )
    (net (code "55") (name "VH") (class "Default")
      (node (ref "C5") (pin "1") (pinfunction "1_1") (pintype "passive"))
      (node (ref "C6") (pin "1") (pinfunction "1_1") (pintype "passive"))
      (node (ref "D1") (pin "2") (pinfunction "2_2") (pintype "passive"))
      (node (ref "FPC2") (pin "24") (pinfunction "24_24") (pintype "passive"))
      (node (ref "FPC2") (pin "25") (pinfunction "25_25") (pintype "passive"))
      (node (ref "FPC2") (pin "5") (pinfunction "5_5") (pintype "passive"))
      (node (ref "FPC2") (pin "6") (pinfunction "6_6") (pintype "passive"))
      (node (ref "R1") (pin "1") (pinfunction "1_1") (pintype "passive"))
    )
    (net (code "56") (name "unconnected-(FPC1-Pad3)") (class "Default")
      (node (ref "FPC1") (pin "3") (pinfunction "3_3") (pintype "passive+no_connect"))
    )
    (net (code "57") (name "unconnected-(FPC1-Pad4)") (class "Default")
      (node (ref "FPC1") (pin "4") (pinfunction "4_4") (pintype "passive+no_connect"))
    )
    (net (code "58") (name "unconnected-(FPC2-Pad7)") (class "Default")
      (node (ref "FPC2") (pin "7") (pinfunction "7_7") (pintype "passive+no_connect"))
    )
    (net (code "59") (name "unconnected-(FPC2-Pad26)") (class "Default")
      (node (ref "FPC2") (pin "26") (pinfunction "26_26") (pintype "passive+no_connect"))
    )
    (net (code "60") (name "unconnected-(FPC2-Pad27)") (class "Default")
      (node (ref "FPC2") (pin "27") (pinfunction "27_27") (pintype "passive+no_connect"))
    )
    (net (code "61") (name "unconnected-(FPC2-Pad31)") (class "Default")
      (node (ref "FPC2") (pin "31") (pinfunction "31_31") (pintype "passive+no_connect"))
    )
    (net (code "62") (name "unconnected-(FPC2-Pad32)") (class "Default")
      (node (ref "FPC2") (pin "32") (pinfunction "32_32") (pintype "passive+no_connect"))
    )
    (net (code "63") (name "unconnected-(H1-Pad11)") (class "Default")
      (node (ref "H1") (pin "11") (pinfunction "11_11") (pintype "passive"))
    )
    (net (code "64") (name "unconnected-(H2-Pad11)") (class "Default")
      (node (ref "H2") (pin "11") (pinfunction "11_11") (pintype "passive"))
    )
    (net (code "65") (name "unconnected-(SW1-Pad3)") (class "Default")
      (node (ref "SW1") (pin "3") (pinfunction "3_3") (pintype "passive+no_connect"))
    )
    (net (code "66") (name "unconnected-(SW2-EP-Pad3)") (class "Default")
      (node (ref "SW2") (pin "3") (pinfunction "EP_3") (pintype "passive+no_connect"))
    )
    (net (code "67") (name "unconnected-(U1-NC-Pad4)") (class "Default")
      (node (ref "U1") (pin "4") (pinfunction "NC_4") (pintype "passive+no_connect"))
    )
    (net (code "68") (name "unconnected-(U2-NC-Pad7)") (class "Default")
      (node (ref "U2") (pin "7") (pinfunction "NC_7") (pintype "passive+no_connect"))
    )
    (net (code "69") (name "unconnected-(U5-IO2-Pad24)") (class "Default")
      (node (ref "U5") (pin "24") (pinfunction "IO2_24") (pintype "passive+no_connect"))
    )
    (net (code "70") (name "unconnected-(U5-IO4-Pad26)") (class "Default")
      (node (ref "U5") (pin "26") (pinfunction "IO4_26") (pintype "passive+no_connect"))
    )
    (net (code "71") (name "unconnected-(U5-IO16-Pad27)") (class "Default")
      (node (ref "U5") (pin "27") (pinfunction "IO16_27") (pintype "passive+no_connect"))
    )
    (net (code "72") (name "unconnected-(U5-NC-Pad17)") (class "Default")
      (node (ref "U5") (pin "17") (pinfunction "NC_17") (pintype "passive+no_connect"))
    )
    (net (code "73") (name "unconnected-(U5-NC-Pad18)") (class "Default")
      (node (ref "U5") (pin "18") (pinfunction "NC_18") (pintype "passive+no_connect"))
    )
    (net (code "74") (name "unconnected-(U5-NC-Pad19)") (class "Default")
      (node (ref "U5") (pin "19") (pinfunction "NC_19") (pintype "passive+no_connect"))
    )
    (net (code "75") (name "unconnected-(U5-NC-Pad20)") (class "Default")
      (node (ref "U5") (pin "20") (pinfunction "NC_20") (pintype "passive+no_connect"))
    )
    (net (code "76") (name "unconnected-(U5-NC-Pad21)") (class "Default")
      (node (ref "U5") (pin "21") (pinfunction "NC_21") (pintype "passive+no_connect"))
    )
    (net (code "77") (name "unconnected-(U5-NC-Pad22)") (class "Default")
      (node (ref "U5") (pin "22") (pinfunction "NC_22") (pintype "passive+no_connect"))
    )
    (net (code "78") (name "unconnected-(U5-NC-Pad32)") (class "Default")
      (node (ref "U5") (pin "32") (pinfunction "NC_32") (pintype "passive+no_connect"))
    )
    (net (code "79") (name "unconnected-(U5-SENSOR_VN-Pad5)") (class "Default")
      (node (ref "U5") (pin "5") (pinfunction "SENSOR_VN_5") (pintype "passive+no_connect"))
    )
    (net (code "80") (name "unconnected-(U6-NC-Pad1)") (class "Default")
      (node (ref "U6") (pin "1") (pinfunction "NC_1") (pintype "passive+no_connect"))
    )
    (net (code "81") (name "unconnected-(U6-NC-Pad5)") (class "Default")
      (node (ref "U6") (pin "5") (pinfunction "NC_5") (pintype "passive+no_connect"))
    )
    (net (code "82") (name "unconnected-(U7-CTS#-Pad9)") (class "Default")
      (node (ref "U7") (pin "9") (pinfunction "CTS#_9") (pintype "passive+no_connect"))
    )
    (net (code "83") (name "unconnected-(U7-DCD#-Pad12)") (class "Default")
      (node (ref "U7") (pin "12") (pinfunction "DCD#_12") (pintype "passive+no_connect"))
    )
    (net (code "84") (name "unconnected-(U7-DSR#-Pad10)") (class "Default")
      (node (ref "U7") (pin "10") (pinfunction "DSR#_10") (pintype "passive+no_connect"))
    )
    (net (code "85") (name "unconnected-(U7-NC-Pad7)") (class "Default")
      (node (ref "U7") (pin "7") (pinfunction "NC_7") (pintype "passive+no_connect"))
    )
    (net (code "86") (name "unconnected-(U7-NC-Pad8)") (class "Default")
      (node (ref "U7") (pin "8") (pinfunction "NC_8") (pintype "passive+no_connect"))
    )
    (net (code "87") (name "unconnected-(U7-R232-Pad15)") (class "Default")
      (node (ref "U7") (pin "15") (pinfunction "R232_15") (pintype "passive+no_connect"))
    )
    (net (code "88") (name "unconnected-(U7-RI#-Pad11)") (class "Default")
      (node (ref "U7") (pin "11") (pinfunction "RI#_11") (pintype "passive+no_connect"))
    )
    (net (code "89") (name "unconnected-(U8-SBU1-PadA8)") (class "Default")
      (node (ref "U8") (pin "A8") (pinfunction "SBU1_A8") (pintype "passive+no_connect"))
    )
    (net (code "90") (name "unconnected-(U8-SBU2-PadB8)") (class "Default")
      (node (ref "U8") (pin "B8") (pinfunction "SBU2_B8") (pintype "passive+no_connect"))
    )
  )
)
